# 2401_Test_Board_V1_1.net
KiCad netlist of a schematic drawn in Altium Designer
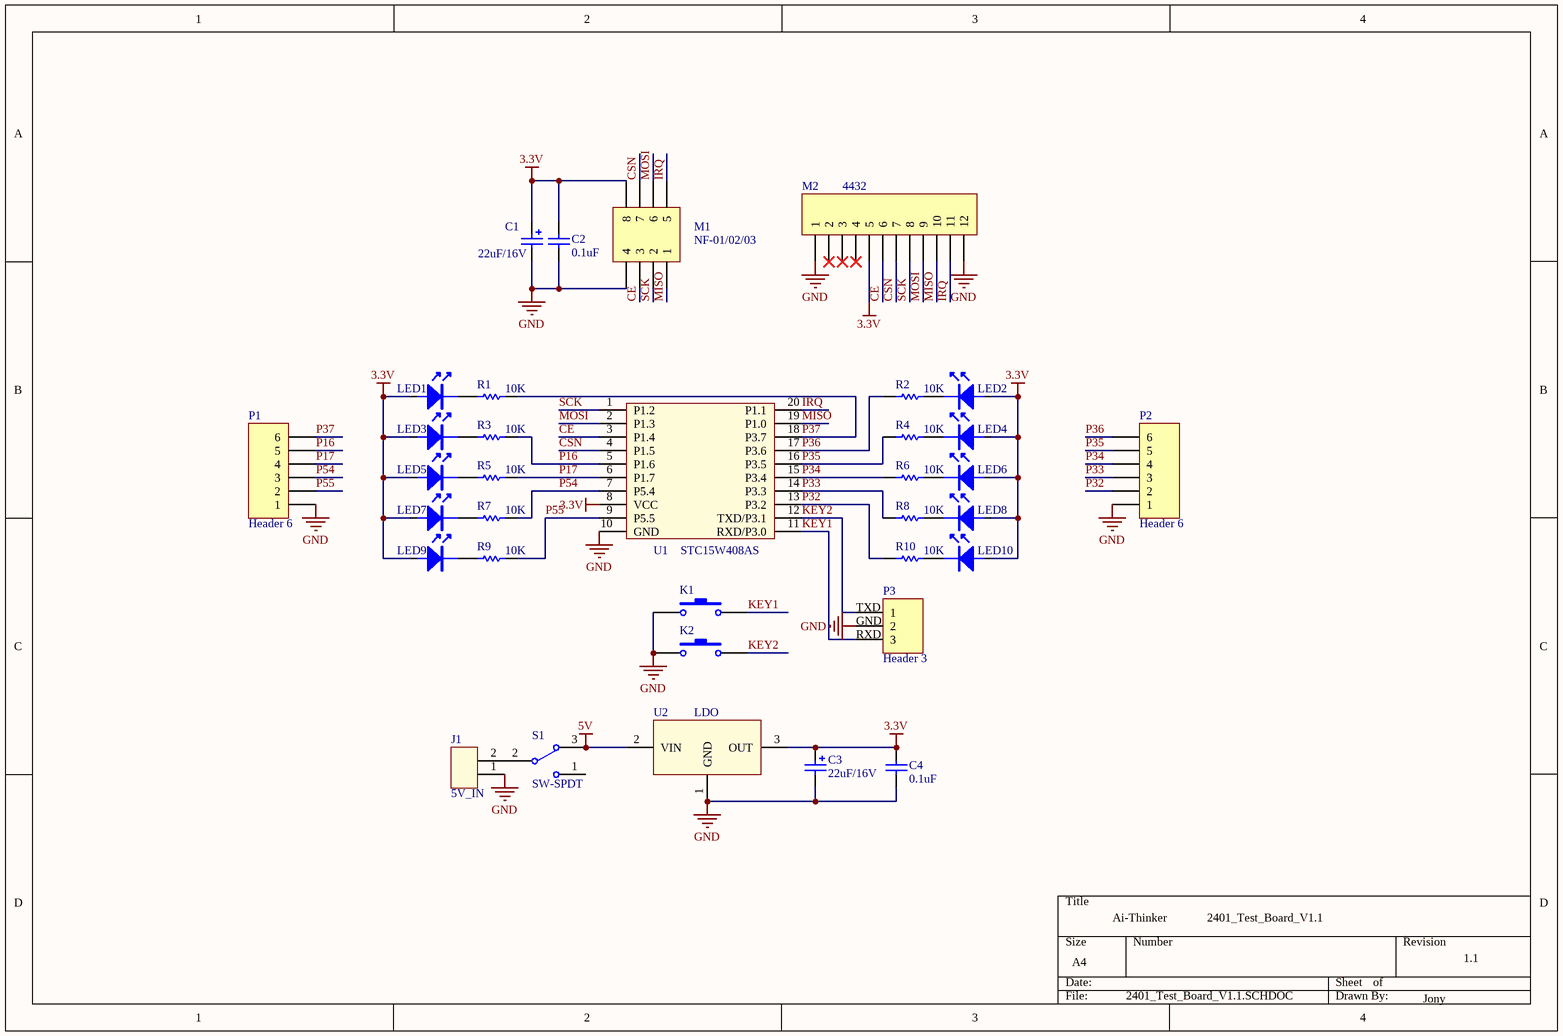
[diagram p0: 2401_Test_Board_V1.1.SCHDOC]

(export (version "E")
  (design (tool "Eeschema 10.0.6"))
  (components
    (comp (ref "C1") (value "22uF/16V") (footprint "CAP4X7") (libsource (lib "Schlib1") (part "Cap+")))
    (comp (ref "C2") (value "0.1uF") (footprint "C0402") (libsource (lib "Schlib1") (part "Cap")))
    (comp (ref "C3") (value "22uF/16V") (footprint "CAP4X7") (libsource (lib "Schlib1") (part "Cap+")))
    (comp (ref "C4") (value "0.1uF") (footprint "C0402") (libsource (lib "Schlib1") (part "Cap")))
    (comp (ref "J1") (value "5V_IN") (footprint "2Pin-YAW396") (libsource (lib "Schlib1") (part "2Pin")))
    (comp (ref "K1")
      (value "~")
      (footprint "KEY-6*6-SMD")
      (fields (field (name "PUBLISHER") "Altium Limited"))
      (libsource (lib "Schlib1") (part "KEY"))
    )
    (comp (ref "K2")
      (value "~")
      (footprint "KEY-6*6-SMD")
      (fields (field (name "PUBLISHER") "Altium Limited"))
      (libsource (lib "Schlib1") (part "KEY"))
    )
    (comp (ref "LED1")
      (value "~")
      (footprint "LED_0603")
      (description "SMD0603 LED")
      (libsource (lib "Schlib1") (part "LED"))
    )
    (comp (ref "LED2")
      (value "~")
      (footprint "LED_0603")
      (description "SMD0603 LED")
      (libsource (lib "Schlib1") (part "LED"))
    )
    (comp (ref "LED3")
      (value "~")
      (footprint "LED_0603")
      (description "SMD0603 LED")
      (libsource (lib "Schlib1") (part "LED"))
    )
    (comp (ref "LED4")
      (value "~")
      (footprint "LED_0603")
      (description "SMD0603 LED")
      (libsource (lib "Schlib1") (part "LED"))
    )
    (comp (ref "LED5")
      (value "~")
      (footprint "LED_0603")
      (description "SMD0603 LED")
      (libsource (lib "Schlib1") (part "LED"))
    )
    (comp (ref "LED6")
      (value "~")
      (footprint "LED_0603")
      (description "SMD0603 LED")
      (libsource (lib "Schlib1") (part "LED"))
    )
    (comp (ref "LED7")
      (value "~")
      (footprint "LED_0603")
      (description "SMD0603 LED")
      (libsource (lib "Schlib1") (part "LED"))
    )
    (comp (ref "LED8")
      (value "~")
      (footprint "LED_0603")
      (description "SMD0603 LED")
      (libsource (lib "Schlib1") (part "LED"))
    )
    (comp (ref "LED9")
      (value "~")
      (footprint "LED_0603")
      (description "SMD0603 LED")
      (libsource (lib "Schlib1") (part "LED"))
    )
    (comp (ref "LED10")
      (value "~")
      (footprint "LED_0603")
      (description "SMD0603 LED")
      (libsource (lib "Schlib1") (part "LED"))
    )
    (comp (ref "M1")
      (value "NF-01/02/03")
      (footprint "HDR2X4_CEN")
      (description "Header, 4-Pin, Dual row")
      (fields (field (name "PUBLISHER") "Altium Limited"))
      (libsource (lib "Miscellaneous Connectors") (part "Header 4X2A"))
    )
    (comp (ref "M2")
      (value "4432")
      (footprint "MHDR1X12")
      (description "Header, 12-Pin")
      (fields (field (name "PUBLISHER") "Altium Limited"))
      (libsource (lib "Miscellaneous Connectors") (part "MHDR1X12"))
    )
    (comp (ref "P1")
      (value "Header 6")
      (footprint "HDR1X6")
      (description "Header, 6-Pin")
      (fields (field (name "PUBLISHER") "Altium Limited"))
      (libsource (lib "Miscellaneous Connectors") (part "Header 6"))
    )
    (comp (ref "P2")
      (value "Header 6")
      (footprint "HDR1X6")
      (description "Header, 6-Pin")
      (fields (field (name "PUBLISHER") "Altium Limited"))
      (libsource (lib "") (part "Header 6_1"))
    )
    (comp (ref "P3")
      (value "Header 3")
      (footprint "HDR1X3")
      (description "Header, 3-Pin")
      (fields (field (name "PUBLISHER") "Altium Limited"))
      (libsource (lib "Miscellaneous Connectors") (part "Header 3"))
    )
    (comp (ref "R1") (value "10K") (footprint "R0402") (libsource (lib "Schlib1") (part "Res")))
    (comp (ref "R2") (value "10K") (footprint "R0402") (libsource (lib "Schlib1") (part "Res")))
    (comp (ref "R3") (value "10K") (footprint "R0402") (libsource (lib "Schlib1") (part "Res")))
    (comp (ref "R4") (value "10K") (footprint "R0402") (libsource (lib "Schlib1") (part "Res")))
    (comp (ref "R5") (value "10K") (footprint "R0402") (libsource (lib "Schlib1") (part "Res")))
    (comp (ref "R6") (value "10K") (footprint "R0402") (libsource (lib "Schlib1") (part "Res")))
    (comp (ref "R7") (value "10K") (footprint "R0402") (libsource (lib "Schlib1") (part "Res")))
    (comp (ref "R8") (value "10K") (footprint "R0402") (libsource (lib "Schlib1") (part "Res")))
    (comp (ref "R9") (value "10K") (footprint "R0402") (libsource (lib "Schlib1") (part "Res")))
    (comp (ref "R10") (value "10K") (footprint "R0402") (libsource (lib "Schlib1") (part "Res")))
    (comp (ref "S1")
      (value "SW-SPDT")
      (footprint "SW-SPDT")
      (description "SPDT Subminiature Toggle Switch, Right Angle Mounting, Vertical Actuation")
      (fields (field (name "PUBLISHER") "Altium Limited"))
      (libsource (lib "Schlib1") (part "SW-SPDT"))
    )
    (comp (ref "U1") (value "STC15W408AS") (libsource (lib "Schlib1") (part "STC15W408AS")))
    (comp (ref "U2") (value "LDO") (libsource (lib "Schlib1") (part "LDO7333")))
  )
  (nets
    (net (code "1") (name "/CE") (class "Default")
      (node (ref "M1") (pin "3") (pinfunction "3_3") (pintype "passive"))
      (node (ref "M2") (pin "6") (pinfunction "6_6") (pintype "passive"))
      (node (ref "U1") (pin "3") (pinfunction "P1.4_3") (pintype "passive"))
    )
    (net (code "2") (name "/CSN") (class "Default")
      (node (ref "M1") (pin "7") (pinfunction "7_7") (pintype "passive"))
      (node (ref "M2") (pin "7") (pinfunction "7_7") (pintype "passive"))
      (node (ref "U1") (pin "4") (pinfunction "P1.5_4") (pintype "passive"))
    )
    (net (code "3") (name "/IRQ") (class "Default")
      (node (ref "M1") (pin "5") (pinfunction "5_5") (pintype "passive"))
      (node (ref "M2") (pin "11") (pinfunction "11_11") (pintype "passive"))
      (node (ref "U1") (pin "20") (pinfunction "P1.1_20") (pintype "passive"))
    )
    (net (code "4") (name "/KEY1") (class "Default")
      (node (ref "K1") (pin "2") (pinfunction "2_2") (pintype "passive"))
      (node (ref "P3") (pin "3") (pinfunction "3_3") (pintype "passive"))
      (node (ref "U1") (pin "11") (pinfunction "RXD/P3.0_11") (pintype "passive"))
    )
    (net (code "5") (name "/KEY2") (class "Default")
      (node (ref "K2") (pin "2") (pinfunction "2_2") (pintype "passive"))
      (node (ref "P3") (pin "1") (pinfunction "1_1") (pintype "passive"))
      (node (ref "U1") (pin "12") (pinfunction "TXD/P3.1_12") (pintype "passive"))
    )
    (net (code "6") (name "/MISO") (class "Default")
      (node (ref "M1") (pin "1") (pinfunction "1_1") (pintype "passive"))
      (node (ref "M2") (pin "10") (pinfunction "10_10") (pintype "passive"))
      (node (ref "U1") (pin "19") (pinfunction "P1.0_19") (pintype "passive"))
    )
    (net (code "7") (name "/MOSI") (class "Default")
      (node (ref "M1") (pin "6") (pinfunction "6_6") (pintype "passive"))
      (node (ref "M2") (pin "9") (pinfunction "9_9") (pintype "passive"))
      (node (ref "U1") (pin "2") (pinfunction "P1.3_2") (pintype "passive"))
    )
    (net (code "8") (name "/P16") (class "Default")
      (node (ref "P1") (pin "5") (pinfunction "5_5") (pintype "passive"))
      (node (ref "R3") (pin "2") (pinfunction "2_2") (pintype "passive"))
      (node (ref "U1") (pin "5") (pinfunction "P1.6_5") (pintype "passive"))
    )
    (net (code "9") (name "/P17") (class "Default")
      (node (ref "P1") (pin "4") (pinfunction "4_4") (pintype "passive"))
      (node (ref "R5") (pin "2") (pinfunction "2_2") (pintype "passive"))
      (node (ref "U1") (pin "6") (pinfunction "P1.7_6") (pintype "passive"))
    )
    (net (code "10") (name "/P32") (class "Default")
      (node (ref "P2") (pin "2") (pinfunction "2_2") (pintype "passive"))
      (node (ref "R10") (pin "1") (pinfunction "1_1") (pintype "passive"))
      (node (ref "U1") (pin "13") (pinfunction "P3.2_13") (pintype "passive"))
    )
    (net (code "11") (name "/P33") (class "Default")
      (node (ref "P2") (pin "3") (pinfunction "3_3") (pintype "passive"))
      (node (ref "R8") (pin "1") (pinfunction "1_1") (pintype "passive"))
      (node (ref "U1") (pin "14") (pinfunction "P3.3_14") (pintype "passive"))
    )
    (net (code "12") (name "/P34") (class "Default")
      (node (ref "P2") (pin "4") (pinfunction "4_4") (pintype "passive"))
      (node (ref "R6") (pin "1") (pinfunction "1_1") (pintype "passive"))
      (node (ref "U1") (pin "15") (pinfunction "P3.4_15") (pintype "passive"))
    )
    (net (code "13") (name "/P35") (class "Default")
      (node (ref "P2") (pin "5") (pinfunction "5_5") (pintype "passive"))
      (node (ref "R4") (pin "1") (pinfunction "1_1") (pintype "passive"))
      (node (ref "U1") (pin "16") (pinfunction "P3.5_16") (pintype "passive"))
    )
    (net (code "14") (name "/P36") (class "Default")
      (node (ref "P2") (pin "6") (pinfunction "6_6") (pintype "passive"))
      (node (ref "R2") (pin "1") (pinfunction "1_1") (pintype "passive"))
      (node (ref "U1") (pin "17") (pinfunction "P3.6_17") (pintype "passive"))
    )
    (net (code "15") (name "/P37") (class "Default")
      (node (ref "P1") (pin "6") (pinfunction "6_6") (pintype "passive"))
      (node (ref "R1") (pin "2") (pinfunction "2_2") (pintype "passive"))
      (node (ref "U1") (pin "18") (pinfunction "P3.7_18") (pintype "passive"))
    )
    (net (code "16") (name "/P54") (class "Default")
      (node (ref "P1") (pin "3") (pinfunction "3_3") (pintype "passive"))
      (node (ref "R7") (pin "2") (pinfunction "2_2") (pintype "passive"))
      (node (ref "U1") (pin "7") (pinfunction "P5.4_7") (pintype "passive"))
    )
    (net (code "17") (name "/P55") (class "Default")
      (node (ref "P1") (pin "2") (pinfunction "2_2") (pintype "passive"))
      (node (ref "R9") (pin "2") (pinfunction "2_2") (pintype "passive"))
      (node (ref "U1") (pin "9") (pinfunction "P5.5_9") (pintype "passive"))
    )
    (net (code "18") (name "/SCK") (class "Default")
      (node (ref "M1") (pin "2") (pinfunction "2_2") (pintype "passive"))
      (node (ref "M2") (pin "8") (pinfunction "8_8") (pintype "passive"))
      (node (ref "U1") (pin "1") (pinfunction "P1.2_1") (pintype "passive"))
    )
    (net (code "19") (name "3.3V") (class "Default")
      (node (ref "C1") (pin "1") (pinfunction "1_1") (pintype "passive"))
      (node (ref "C2") (pin "2") (pinfunction "2_2") (pintype "passive"))
      (node (ref "C3") (pin "1") (pinfunction "1_1") (pintype "passive"))
      (node (ref "C4") (pin "2") (pinfunction "2_2") (pintype "passive"))
      (node (ref "LED1") (pin "1") (pinfunction "A_1") (pintype "passive"))
      (node (ref "LED10") (pin "1") (pinfunction "A_1") (pintype "passive"))
      (node (ref "LED2") (pin "1") (pinfunction "A_1") (pintype "passive"))
      (node (ref "LED3") (pin "1") (pinfunction "A_1") (pintype "passive"))
      (node (ref "LED4") (pin "1") (pinfunction "A_1") (pintype "passive"))
      (node (ref "LED5") (pin "1") (pinfunction "A_1") (pintype "passive"))
      (node (ref "LED6") (pin "1") (pinfunction "A_1") (pintype "passive"))
      (node (ref "LED7") (pin "1") (pinfunction "A_1") (pintype "passive"))
      (node (ref "LED8") (pin "1") (pinfunction "A_1") (pintype "passive"))
      (node (ref "LED9") (pin "1") (pinfunction "A_1") (pintype "passive"))
      (node (ref "M1") (pin "8") (pinfunction "8_8") (pintype "passive"))
      (node (ref "M2") (pin "5") (pinfunction "5_5") (pintype "passive"))
      (node (ref "U1") (pin "8") (pinfunction "VCC_8") (pintype "passive"))
      (node (ref "U2") (pin "3") (pinfunction "OUT_3") (pintype "passive"))
    )
    (net (code "20") (name "5V") (class "Default")
      (node (ref "S1") (pin "3") (pinfunction "3_3") (pintype "passive"))
      (node (ref "U2") (pin "2") (pinfunction "VIN_2") (pintype "passive"))
    )
    (net (code "21") (name "GND") (class "Default")
      (node (ref "C1") (pin "2") (pinfunction "2_2") (pintype "passive"))
      (node (ref "C2") (pin "1") (pinfunction "1_1") (pintype "passive"))
      (node (ref "C3") (pin "2") (pinfunction "2_2") (pintype "passive"))
      (node (ref "C4") (pin "1") (pinfunction "1_1") (pintype "passive"))
      (node (ref "J1") (pin "1") (pintype "passive"))
      (node (ref "K1") (pin "1") (pinfunction "1_1") (pintype "passive"))
      (node (ref "K2") (pin "1") (pinfunction "1_1") (pintype "passive"))
      (node (ref "M1") (pin "4") (pinfunction "4_4") (pintype "passive"))
      (node (ref "M2") (pin "1") (pinfunction "1_1") (pintype "passive"))
      (node (ref "M2") (pin "12") (pinfunction "12_12") (pintype "passive"))
      (node (ref "P1") (pin "1") (pinfunction "1_1") (pintype "passive"))
      (node (ref "P2") (pin "1") (pinfunction "1_1") (pintype "passive"))
      (node (ref "P3") (pin "2") (pinfunction "2_2") (pintype "passive"))
      (node (ref "U1") (pin "10") (pinfunction "GND_10") (pintype "passive"))
      (node (ref "U2") (pin "1") (pinfunction "GND_1") (pintype "passive"))
    )
    (net (code "22") (name "Net-(J1-Pad2)") (class "Default")
      (node (ref "J1") (pin "2") (pintype "passive"))
      (node (ref "S1") (pin "2") (pinfunction "2_2") (pintype "passive"))
    )
    (net (code "23") (name "Net-(LED1-K)") (class "Default")
      (node (ref "LED1") (pin "2") (pinfunction "K_2") (pintype "passive"))
      (node (ref "R1") (pin "1") (pinfunction "1_1") (pintype "passive"))
    )
    (net (code "24") (name "Net-(LED2-K)") (class "Default")
      (node (ref "LED2") (pin "2") (pinfunction "K_2") (pintype "passive"))
      (node (ref "R2") (pin "2") (pinfunction "2_2") (pintype "passive"))
    )
    (net (code "25") (name "Net-(LED3-K)") (class "Default")
      (node (ref "LED3") (pin "2") (pinfunction "K_2") (pintype "passive"))
      (node (ref "R3") (pin "1") (pinfunction "1_1") (pintype "passive"))
    )
    (net (code "26") (name "Net-(LED4-K)") (class "Default")
      (node (ref "LED4") (pin "2") (pinfunction "K_2") (pintype "passive"))
      (node (ref "R4") (pin "2") (pinfunction "2_2") (pintype "passive"))
    )
    (net (code "27") (name "Net-(LED5-K)") (class "Default")
      (node (ref "LED5") (pin "2") (pinfunction "K_2") (pintype "passive"))
      (node (ref "R5") (pin "1") (pinfunction "1_1") (pintype "passive"))
    )
    (net (code "28") (name "Net-(LED6-K)") (class "Default")
      (node (ref "LED6") (pin "2") (pinfunction "K_2") (pintype "passive"))
      (node (ref "R6") (pin "2") (pinfunction "2_2") (pintype "passive"))
    )
    (net (code "29") (name "Net-(LED7-K)") (class "Default")
      (node (ref "LED7") (pin "2") (pinfunction "K_2") (pintype "passive"))
      (node (ref "R7") (pin "1") (pinfunction "1_1") (pintype "passive"))
    )
    (net (code "30") (name "Net-(LED8-K)") (class "Default")
      (node (ref "LED8") (pin "2") (pinfunction "K_2") (pintype "passive"))
      (node (ref "R8") (pin "2") (pinfunction "2_2") (pintype "passive"))
    )
    (net (code "31") (name "Net-(LED9-K)") (class "Default")
      (node (ref "LED9") (pin "2") (pinfunction "K_2") (pintype "passive"))
      (node (ref "R9") (pin "1") (pinfunction "1_1") (pintype "passive"))
    )
    (net (code "32") (name "Net-(LED10-K)") (class "Default")
      (node (ref "LED10") (pin "2") (pinfunction "K_2") (pintype "passive"))
      (node (ref "R10") (pin "2") (pinfunction "2_2") (pintype "passive"))
    )
    (net (code "33") (name "unconnected-(M2-Pad2)") (class "Default")
      (node (ref "M2") (pin "2") (pinfunction "2_2") (pintype "passive+no_connect"))
    )
    (net (code "34") (name "unconnected-(M2-Pad3)") (class "Default")
      (node (ref "M2") (pin "3") (pinfunction "3_3") (pintype "passive+no_connect"))
    )
    (net (code "35") (name "unconnected-(M2-Pad4)") (class "Default")
      (node (ref "M2") (pin "4") (pinfunction "4_4") (pintype "passive+no_connect"))
    )
    (net (code "36") (name "unconnected-(S1-Pad1)") (class "Default")
      (node (ref "S1") (pin "1") (pinfunction "1_1") (pintype "passive"))
    )
  )
)
